# ethero_v2.net
KiCad netlist of a schematic drawn in EAGLE
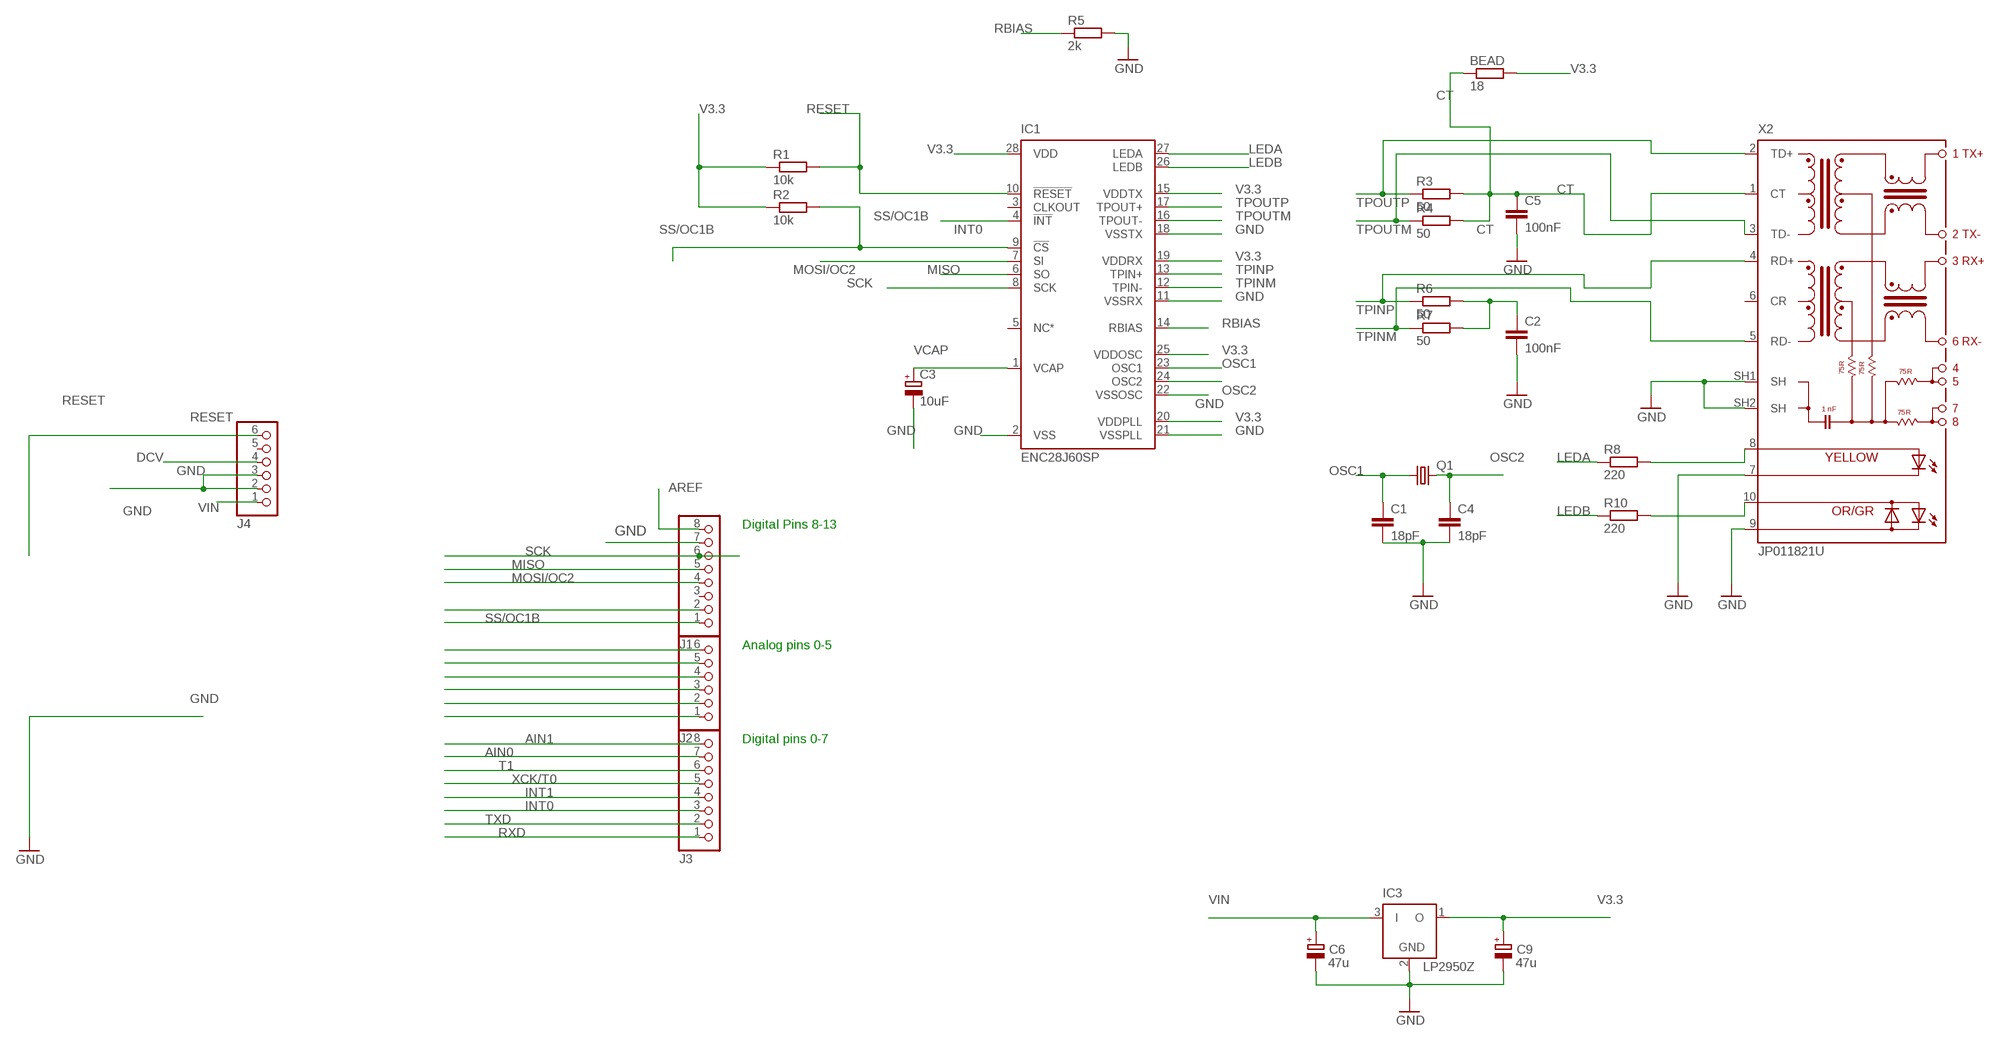
[diagram p0: schematic, sheet 1]

(export (version "E")
  (design (tool "Eeschema 10.0.6"))
  (components
    (comp (ref "BEAD")
      (value "18")
      (footprint "eagle-import:0204_7")
      (libsource (lib "eagle-import") (part "R-EU_0204/7"))
    )
    (comp (ref "C1")
      (value "18pF")
      (footprint "eagle-import:C025-025X050")
      (libsource (lib "eagle-import") (part "C-EU025-025X050"))
    )
    (comp (ref "C2")
      (value "100nF")
      (footprint "eagle-import:C025-025X050")
      (libsource (lib "eagle-import") (part "C-EU025-025X050"))
    )
    (comp (ref "C3")
      (value "10uF")
      (footprint "eagle-import:E5-5")
      (libsource (lib "eagle-import") (part "CPOL-EUE5-5"))
    )
    (comp (ref "C4")
      (value "18pF")
      (footprint "eagle-import:C025-025X050")
      (libsource (lib "eagle-import") (part "C-EU025-025X050"))
    )
    (comp (ref "C5")
      (value "100nF")
      (footprint "eagle-import:C025-025X050")
      (libsource (lib "eagle-import") (part "C-EU025-025X050"))
    )
    (comp (ref "C6")
      (value "47u")
      (footprint "eagle-import:E3,5-8")
      (libsource (lib "eagle-import") (part "CPOL-EUE3.5-8"))
    )
    (comp (ref "C9")
      (value "47u")
      (footprint "eagle-import:E3,5-8")
      (libsource (lib "eagle-import") (part "CPOL-EUE3.5-8"))
    )
    (comp (ref "IC1")
      (value "ENC28J60SP")
      (footprint "eagle-import:DIL28-3")
      (fields (field (name "MF") "MICROCHIP") (field (name "MPN") "ENC28J60/SP"))
      (libsource (lib "eagle-import") (part "ENC28J60SP"))
    )
    (comp (ref "IC3")
      (value "LP2950Z")
      (footprint "eagle-import:TO92")
      (libsource (lib "eagle-import") (part "LP2950Z"))
    )
    (comp (ref "J1")
      (value "PINHD-1X8")
      (footprint "eagle-import:1X08")
      (libsource (lib "eagle-import") (part "PINHD-1X8"))
    )
    (comp (ref "J2")
      (value "PINHD-1X6")
      (footprint "eagle-import:1X06")
      (libsource (lib "eagle-import") (part "PINHD-1X6"))
    )
    (comp (ref "J3")
      (value "PINHD-1X8")
      (footprint "eagle-import:1X08")
      (libsource (lib "eagle-import") (part "PINHD-1X8"))
    )
    (comp (ref "J4")
      (value "PINHD-1X6")
      (footprint "eagle-import:1X06")
      (libsource (lib "eagle-import") (part "PINHD-1X6"))
    )
    (comp (ref "Q1")
      (value "CRYSTALHC18U-V")
      (footprint "eagle-import:HC18U-V")
      (libsource (lib "eagle-import") (part "CRYSTALHC18U-V"))
    )
    (comp (ref "R1")
      (value "10k")
      (footprint "eagle-import:0204_7")
      (libsource (lib "eagle-import") (part "R-EU_0204/7"))
    )
    (comp (ref "R2")
      (value "10k")
      (footprint "eagle-import:0204_7")
      (libsource (lib "eagle-import") (part "R-EU_0204/7"))
    )
    (comp (ref "R3")
      (value "50")
      (footprint "eagle-import:0204_7")
      (libsource (lib "eagle-import") (part "R-EU_0204/7"))
    )
    (comp (ref "R4")
      (value "50")
      (footprint "eagle-import:0204_7")
      (libsource (lib "eagle-import") (part "R-EU_0204/7"))
    )
    (comp (ref "R5")
      (value "2k")
      (footprint "eagle-import:0204_7")
      (libsource (lib "eagle-import") (part "R-EU_0204/7"))
    )
    (comp (ref "R6")
      (value "50")
      (footprint "eagle-import:0204_7")
      (libsource (lib "eagle-import") (part "R-EU_0204/7"))
    )
    (comp (ref "R7")
      (value "50")
      (footprint "eagle-import:0204_7")
      (libsource (lib "eagle-import") (part "R-EU_0204/7"))
    )
    (comp (ref "R8")
      (value "220")
      (footprint "eagle-import:0204_7")
      (libsource (lib "eagle-import") (part "R-EU_0204/7"))
    )
    (comp (ref "R10")
      (value "220")
      (footprint "eagle-import:0204_7")
      (libsource (lib "eagle-import") (part "R-EU_0204/7"))
    )
    (comp (ref "X2")
      (value "JP011821U")
      (footprint "eagle-import:JP")
      (libsource (lib "eagle-import") (part "JP011821U"))
    )
  )
  (nets
    (net (code "1") (name "/AIN0") (class "Default")
      (node (ref "J3") (pin "7") (pinfunction "7_7") (pintype "passive"))
    )
    (net (code "2") (name "/AIN1") (class "Default")
      (node (ref "J3") (pin "8") (pinfunction "8_8") (pintype "passive"))
    )
    (net (code "3") (name "/AREF") (class "Default")
      (node (ref "J1") (pin "8") (pinfunction "8_8") (pintype "passive"))
    )
    (net (code "4") (name "/CT") (class "Default")
      (node (ref "BEAD") (pin "1") (pinfunction "1_1") (pintype "passive"))
      (node (ref "C5") (pin "1") (pinfunction "1_1") (pintype "passive"))
      (node (ref "R3") (pin "2") (pinfunction "2_2") (pintype "passive"))
      (node (ref "R4") (pin "2") (pinfunction "2_2") (pintype "passive"))
      (node (ref "X2") (pin "1") (pinfunction "CT_1") (pintype "input"))
    )
    (net (code "5") (name "/DCV") (class "Default")
      (node (ref "J4") (pin "4") (pinfunction "4_4") (pintype "passive"))
    )
    (net (code "6") (name "/INT0") (class "Default")
      (node (ref "IC1") (pin "4") (pinfunction "~{INT}_4") (pintype "output"))
      (node (ref "J3") (pin "3") (pinfunction "3_3") (pintype "passive"))
    )
    (net (code "7") (name "/INT1") (class "Default")
      (node (ref "J3") (pin "4") (pinfunction "4_4") (pintype "passive"))
    )
    (net (code "8") (name "/LEDA") (class "Default")
      (node (ref "IC1") (pin "27") (pinfunction "LEDA_27") (pintype "output"))
      (node (ref "R8") (pin "1") (pinfunction "1_1") (pintype "passive"))
    )
    (net (code "9") (name "/LEDB") (class "Default")
      (node (ref "IC1") (pin "26") (pinfunction "LEDB_26") (pintype "output"))
      (node (ref "R10") (pin "1") (pinfunction "1_1") (pintype "passive"))
    )
    (net (code "10") (name "/MISO") (class "Default")
      (node (ref "IC1") (pin "6") (pinfunction "SO_6") (pintype "output"))
      (node (ref "J1") (pin "5") (pinfunction "5_5") (pintype "passive"))
    )
    (net (code "11") (name "/MOSI{slash}OC2") (class "Default")
      (node (ref "IC1") (pin "7") (pinfunction "SI_7") (pintype "input"))
      (node (ref "J1") (pin "4") (pinfunction "4_4") (pintype "passive"))
    )
    (net (code "12") (name "/OSC1") (class "Default")
      (node (ref "C1") (pin "1") (pinfunction "1_1") (pintype "passive"))
      (node (ref "IC1") (pin "23") (pinfunction "OSC1_23") (pintype "input"))
      (node (ref "Q1") (pin "1") (pinfunction "1_1") (pintype "passive"))
    )
    (net (code "13") (name "/OSC2") (class "Default")
      (node (ref "C4") (pin "1") (pinfunction "1_1") (pintype "passive"))
      (node (ref "IC1") (pin "24") (pinfunction "OSC2_24") (pintype "output"))
      (node (ref "Q1") (pin "2") (pinfunction "2_2") (pintype "passive"))
    )
    (net (code "14") (name "/RBIAS") (class "Default")
      (node (ref "IC1") (pin "14") (pinfunction "RBIAS_14") (pintype "input"))
      (node (ref "R5") (pin "1") (pinfunction "1_1") (pintype "passive"))
    )
    (net (code "15") (name "/RESET") (class "Default")
      (node (ref "IC1") (pin "10") (pinfunction "~{RESET}_10") (pintype "input"))
      (node (ref "J4") (pin "6") (pinfunction "6_6") (pintype "passive"))
      (node (ref "R1") (pin "2") (pinfunction "2_2") (pintype "passive"))
    )
    (net (code "16") (name "/RXD") (class "Default")
      (node (ref "J3") (pin "1") (pinfunction "1_1") (pintype "passive"))
    )
    (net (code "17") (name "/SCK") (class "Default")
      (node (ref "IC1") (pin "8") (pinfunction "SCK_8") (pintype "input"))
      (node (ref "J1") (pin "6") (pinfunction "6_6") (pintype "passive"))
    )
    (net (code "18") (name "/SS{slash}OC1B") (class "Default")
      (node (ref "IC1") (pin "9") (pinfunction "~{CS}_9") (pintype "input"))
      (node (ref "J1") (pin "1") (pinfunction "1_1") (pintype "passive"))
      (node (ref "R2") (pin "2") (pinfunction "2_2") (pintype "passive"))
    )
    (net (code "19") (name "/T1") (class "Default")
      (node (ref "J3") (pin "6") (pinfunction "6_6") (pintype "passive"))
    )
    (net (code "20") (name "/TPINM") (class "Default")
      (node (ref "IC1") (pin "12") (pinfunction "TPIN-_12") (pintype "input"))
      (node (ref "R7") (pin "1") (pinfunction "1_1") (pintype "passive"))
      (node (ref "X2") (pin "5") (pinfunction "RD-_5") (pintype "input"))
    )
    (net (code "21") (name "/TPINP") (class "Default")
      (node (ref "IC1") (pin "13") (pinfunction "TPIN+_13") (pintype "input"))
      (node (ref "R6") (pin "1") (pinfunction "1_1") (pintype "passive"))
      (node (ref "X2") (pin "4") (pinfunction "RD+_4") (pintype "input"))
    )
    (net (code "22") (name "/TPOUTM") (class "Default")
      (node (ref "IC1") (pin "16") (pinfunction "TPOUT-_16") (pintype "output"))
      (node (ref "R4") (pin "1") (pinfunction "1_1") (pintype "passive"))
      (node (ref "X2") (pin "3") (pinfunction "TD-_3") (pintype "input"))
    )
    (net (code "23") (name "/TPOUTP") (class "Default")
      (node (ref "IC1") (pin "17") (pinfunction "TPOUT+_17") (pintype "output"))
      (node (ref "R3") (pin "1") (pinfunction "1_1") (pintype "passive"))
      (node (ref "X2") (pin "2") (pinfunction "TD+_2") (pintype "input"))
    )
    (net (code "24") (name "/TXD") (class "Default")
      (node (ref "J3") (pin "2") (pinfunction "2_2") (pintype "passive"))
    )
    (net (code "25") (name "/V3.3") (class "Default")
      (node (ref "BEAD") (pin "2") (pinfunction "2_2") (pintype "passive"))
      (node (ref "C9") (pin "+") (pinfunction "+_+") (pintype "passive"))
      (node (ref "IC1") (pin "15") (pinfunction "VDDTX_15") (pintype "input"))
      (node (ref "IC1") (pin "19") (pinfunction "VDDRX_19") (pintype "input"))
      (node (ref "IC1") (pin "20") (pinfunction "VDDPLL_20") (pintype "input"))
      (node (ref "IC1") (pin "25") (pinfunction "VDDOSC_25") (pintype "input"))
      (node (ref "IC1") (pin "28") (pinfunction "VDD_28") (pintype "input"))
      (node (ref "IC3") (pin "1") (pinfunction "O_1") (pintype "input"))
      (node (ref "R1") (pin "1") (pinfunction "1_1") (pintype "passive"))
      (node (ref "R2") (pin "1") (pinfunction "1_1") (pintype "passive"))
    )
    (net (code "26") (name "/VCAP") (class "Default")
      (node (ref "C3") (pin "+") (pinfunction "+_+") (pintype "passive"))
      (node (ref "IC1") (pin "1") (pinfunction "VCAP_1") (pintype "input"))
    )
    (net (code "27") (name "/VIN") (class "Default")
      (node (ref "C6") (pin "+") (pinfunction "+_+") (pintype "passive"))
      (node (ref "IC3") (pin "3") (pinfunction "I_3") (pintype "input"))
      (node (ref "J4") (pin "1") (pinfunction "1_1") (pintype "passive"))
    )
    (net (code "28") (name "/XCK{slash}T0") (class "Default")
      (node (ref "J3") (pin "5") (pinfunction "5_5") (pintype "passive"))
    )
    (net (code "29") (name "GND") (class "Default")
      (node (ref "C1") (pin "2") (pinfunction "2_2") (pintype "passive"))
      (node (ref "C2") (pin "2") (pinfunction "2_2") (pintype "passive"))
      (node (ref "C3") (pin "-") (pinfunction "-_-") (pintype "passive"))
      (node (ref "C4") (pin "2") (pinfunction "2_2") (pintype "passive"))
      (node (ref "C5") (pin "2") (pinfunction "2_2") (pintype "passive"))
      (node (ref "C6") (pin "-") (pinfunction "-_-") (pintype "passive"))
      (node (ref "C9") (pin "-") (pinfunction "-_-") (pintype "passive"))
      (node (ref "IC1") (pin "11") (pinfunction "VSSRX_11") (pintype "input"))
      (node (ref "IC1") (pin "18") (pinfunction "VSSTX_18") (pintype "input"))
      (node (ref "IC1") (pin "2") (pinfunction "VSS_2") (pintype "input"))
      (node (ref "IC1") (pin "21") (pinfunction "VSSPLL_21") (pintype "input"))
      (node (ref "IC1") (pin "22") (pinfunction "VSSOSC_22") (pintype "input"))
      (node (ref "IC3") (pin "2") (pinfunction "GND_2") (pintype "power_in"))
      (node (ref "J1") (pin "7") (pinfunction "7_7") (pintype "passive"))
      (node (ref "J4") (pin "2") (pinfunction "2_2") (pintype "passive"))
      (node (ref "J4") (pin "3") (pinfunction "3_3") (pintype "passive"))
      (node (ref "R5") (pin "2") (pinfunction "2_2") (pintype "passive"))
      (node (ref "X2") (pin "7") (pinfunction "C-Y_7") (pintype "input"))
      (node (ref "X2") (pin "9") (pinfunction "A-O_C-G_9") (pintype "input"))
      (node (ref "X2") (pin "SH1") (pinfunction "SH_SH1") (pintype "input"))
      (node (ref "X2") (pin "SH2") (pinfunction "SH_SH2") (pintype "input"))
    )
    (net (code "30") (name "Net-(C2-Pad1)") (class "Default")
      (node (ref "C2") (pin "1") (pinfunction "1_1") (pintype "passive"))
      (node (ref "R6") (pin "2") (pinfunction "2_2") (pintype "passive"))
      (node (ref "R7") (pin "2") (pinfunction "2_2") (pintype "passive"))
    )
    (net (code "31") (name "Net-(X2-A-Y)") (class "Default")
      (node (ref "R8") (pin "2") (pinfunction "2_2") (pintype "passive"))
      (node (ref "X2") (pin "8") (pinfunction "A-Y_8") (pintype "input"))
    )
    (net (code "32") (name "Net-(X2-C-O_A-G)") (class "Default")
      (node (ref "R10") (pin "2") (pinfunction "2_2") (pintype "passive"))
      (node (ref "X2") (pin "10") (pinfunction "C-O_A-G_10") (pintype "input"))
    )
    (net (code "33") (name "unconnected-(IC1-CLKOUT-Pad3)") (class "Default")
      (node (ref "IC1") (pin "3") (pinfunction "CLKOUT_3") (pintype "output"))
    )
    (net (code "34") (name "unconnected-(IC1-NC*-Pad5)") (class "Default")
      (node (ref "IC1") (pin "5") (pinfunction "NC*_5") (pintype "output"))
    )
    (net (code "35") (name "unconnected-(J1-Pad2)") (class "Default")
      (node (ref "J1") (pin "2") (pinfunction "2_2") (pintype "passive"))
    )
    (net (code "36") (name "unconnected-(J1-Pad3)") (class "Default")
      (node (ref "J1") (pin "3") (pinfunction "3_3") (pintype "passive"))
    )
    (net (code "37") (name "unconnected-(J2-Pad1)") (class "Default")
      (node (ref "J2") (pin "1") (pinfunction "1_1") (pintype "passive"))
    )
    (net (code "38") (name "unconnected-(J2-Pad2)") (class "Default")
      (node (ref "J2") (pin "2") (pinfunction "2_2") (pintype "passive"))
    )
    (net (code "39") (name "unconnected-(J2-Pad3)") (class "Default")
      (node (ref "J2") (pin "3") (pinfunction "3_3") (pintype "passive"))
    )
    (net (code "40") (name "unconnected-(J2-Pad4)") (class "Default")
      (node (ref "J2") (pin "4") (pinfunction "4_4") (pintype "passive"))
    )
    (net (code "41") (name "unconnected-(J2-Pad5)") (class "Default")
      (node (ref "J2") (pin "5") (pinfunction "5_5") (pintype "passive"))
    )
    (net (code "42") (name "unconnected-(J2-Pad6)") (class "Default")
      (node (ref "J2") (pin "6") (pinfunction "6_6") (pintype "passive"))
    )
    (net (code "43") (name "unconnected-(J4-Pad5)") (class "Default")
      (node (ref "J4") (pin "5") (pinfunction "5_5") (pintype "passive"))
    )
    (net (code "44") (name "unconnected-(X2-CR-Pad6)") (class "Default")
      (node (ref "X2") (pin "6") (pinfunction "CR_6") (pintype "input"))
    )
  )
)
